# hub_board.net
KiCad netlist of a schematic drawn in Altium Designer
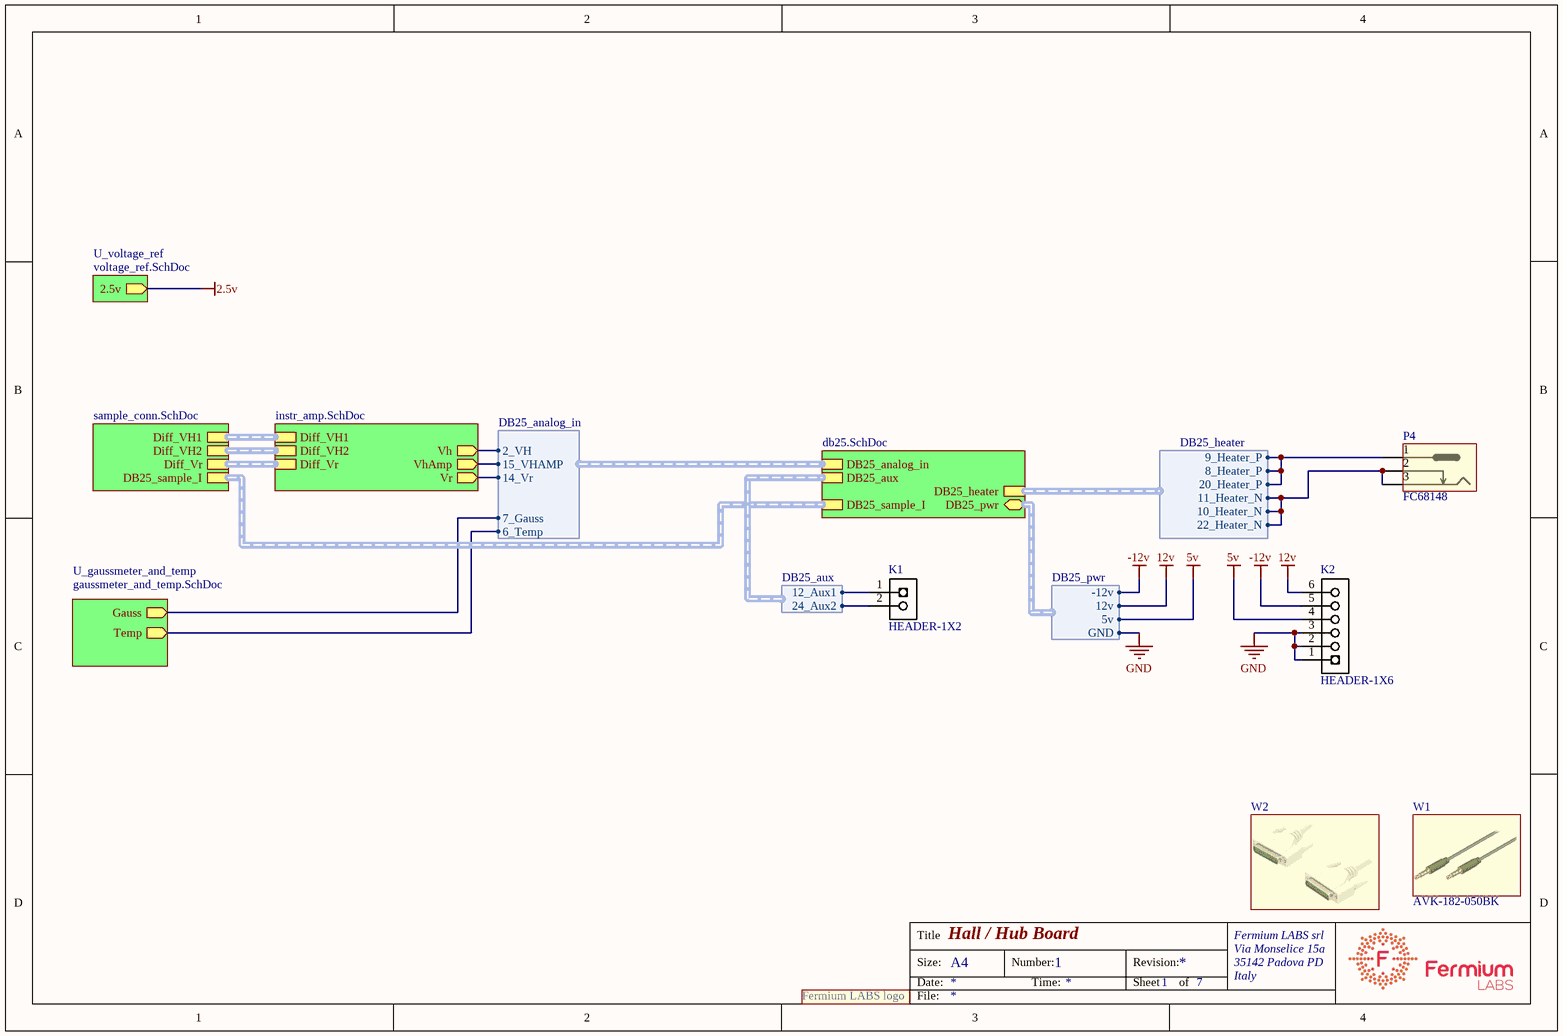
[diagram p0: hub_board.SchDoc]

(export (version "E")
  (design (tool "Eeschema 10.0.6"))
  (components
    (comp (ref "K1")
      (value "HEADER-1X2")
      (footprint "HEADER-1X2")
      (libsource (lib "TH Connectors") (part "HEADER-1X2"))
    )
    (comp (ref "K2")
      (value "HEADER-1X6")
      (footprint "HEADER-1X6")
      (libsource (lib "TH Connectors") (part "HEADER-1X6"))
    )
    (comp (ref "logo")
      (value "fermiumlabs-logo")
      (footprint "frm-med")
      (libsource (lib "custom_components") (part "fermiumlabs-logo"))
    )
    (comp (ref "P4")
      (value "~")
      (footprint "custom_components:dc-jack")
      (fields
        (field (name "SUPPLIER PART NUMBER 1") "FC68148")
        (field (name "MANUFACTURER") "CLIFF")
        (field (name "MANUFACTURER PART NUMBER") "DC-10A FC68148")
      )
      (libsource (lib "custom_components") (part "jackdc"))
    )
    (comp (ref "W1")
      (value "AVK-182-050BK")
      (fields (field (name "MANUFACTURER PART NUMBER") "63824") (field (name "MANUFACTURER") "GOOBAY"))
      (libsource (lib "custom_components") (part "AVK-182-050BK"))
    )
    (comp (ref "W2")
      (value "~")
      (fields (field (name "MANUFACTURER") "BQ CABLE") (field (name "MANUFACTURER PART NUMBER") "CAB-25WW/2"))
      (libsource (lib "custom_components") (part "CAB-25WW/2"))
    )
  )
  (nets
    (net (code "5") (name "-12v") (class "Default") (node (ref "K2") (pin "5") (pintype "passive")))
    (net (code "9") (name "/10_Heater_N") (class "Default")
      (node (ref "P4") (pin "2") (pinfunction "2_2") (pintype "passive"))
      (node (ref "P4") (pin "3") (pinfunction "3_3") (pintype "passive"))
    )
    (net (code "10") (name "/12_Aux1") (class "Default") (node (ref "K1") (pin "1") (pintype "passive")))
    (net (code "13") (name "/20_Heater_P") (class "Default")
      (node (ref "P4") (pin "1") (pinfunction "1_1") (pintype "passive"))
    )
    (net (code "14") (name "/24_Aux2") (class "Default") (node (ref "K1") (pin "2") (pintype "passive")))
    (net (code "24") (name "5v") (class "Default") (node (ref "K2") (pin "4") (pintype "passive")))
    (net (code "25") (name "12v") (class "Default") (node (ref "K2") (pin "6") (pintype "passive")))
    (net (code "26") (name "GND") (class "Default")
      (node (ref "K2") (pin "1") (pintype "passive"))
      (node (ref "K2") (pin "2") (pintype "passive"))
      (node (ref "K2") (pin "3") (pintype "passive"))
    )
  )
)
